# LOGIC_CONNECTOR.net
KiCad netlist of a schematic drawn in Altium Designer
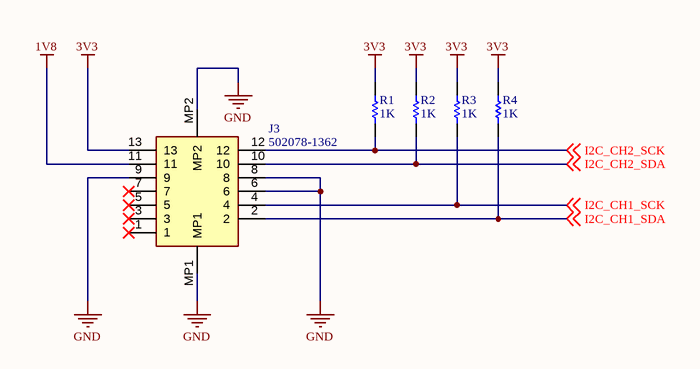
[diagram p0: LOGIC_CONNECTOR.SchDoc]

(export (version "E")
  (design (tool "Eeschema 10.0.6"))
  (components
    (comp (ref "J3")
      (value "502078-1362")
      (footprint "SamacSys:5020781362")
      (description "Connector")
      (fields (field (name "MOUSER PART NUMBER") "538-502078-1362"))
      (libsource (lib "*") (part "502078-1362"))
    )
    (comp (ref "R1")
      (value "1K")
      (footprint "RESC1005X40X25LL05T10")
      (fields (field (name "PART NUMBER") "RC0402JR-071KL") (field (name "MANUFACTURER") "Yageo / Phycomp"))
      (libsource (lib "Altium Content Vault") (part "RES"))
    )
    (comp (ref "R2")
      (value "1K")
      (footprint "RESC1005X40X25LL05T10")
      (fields (field (name "PART NUMBER") "RC0402JR-071KL") (field (name "MANUFACTURER") "Yageo / Phycomp"))
      (libsource (lib "Altium Content Vault") (part "RES"))
    )
    (comp (ref "R3")
      (value "1K")
      (footprint "RESC1005X40X25LL05T10")
      (fields (field (name "PART NUMBER") "RC0402JR-071KL") (field (name "MANUFACTURER") "Yageo / Phycomp"))
      (libsource (lib "Altium Content Vault") (part "RES"))
    )
    (comp (ref "R4")
      (value "1K")
      (footprint "RESC1005X40X25LL05T10")
      (fields (field (name "PART NUMBER") "RC0402JR-071KL") (field (name "MANUFACTURER") "Yageo / Phycomp"))
      (libsource (lib "Altium Content Vault") (part "RES"))
    )
  )
  (nets
    (net (code "1") (name "1V8") (class "Default")
      (node (ref "J3") (pin "11") (pinfunction "11_11") (pintype "passive"))
    )
    (net (code "2") (name "3V3") (class "Default")
      (node (ref "J3") (pin "13") (pinfunction "13_13") (pintype "passive"))
      (node (ref "R1") (pin "2") (pinfunction "2_2") (pintype "passive"))
      (node (ref "R2") (pin "2") (pinfunction "2_2") (pintype "passive"))
      (node (ref "R3") (pin "2") (pinfunction "2_2") (pintype "passive"))
      (node (ref "R4") (pin "2") (pinfunction "2_2") (pintype "passive"))
    )
    (net (code "3") (name "GND") (class "Default")
      (node (ref "J3") (pin "6") (pinfunction "6_6") (pintype "passive"))
      (node (ref "J3") (pin "8") (pinfunction "8_8") (pintype "passive"))
      (node (ref "J3") (pin "9") (pinfunction "9_9") (pintype "passive"))
      (node (ref "J3") (pin "MP1") (pinfunction "MP1_MP1") (pintype "passive"))
      (node (ref "J3") (pin "MP2") (pinfunction "MP2_MP2") (pintype "passive"))
    )
    (net (code "4") (name "I2C_CH1_SCK") (class "Default")
      (node (ref "J3") (pin "4") (pinfunction "4_4") (pintype "passive"))
      (node (ref "R3") (pin "1") (pinfunction "1_1") (pintype "passive"))
    )
    (net (code "5") (name "I2C_CH1_SDA") (class "Default")
      (node (ref "J3") (pin "2") (pinfunction "2_2") (pintype "passive"))
      (node (ref "R4") (pin "1") (pinfunction "1_1") (pintype "passive"))
    )
    (net (code "6") (name "I2C_CH2_SCK") (class "Default")
      (node (ref "J3") (pin "12") (pinfunction "12_12") (pintype "passive"))
      (node (ref "R1") (pin "1") (pinfunction "1_1") (pintype "passive"))
    )
    (net (code "7") (name "I2C_CH2_SDA") (class "Default")
      (node (ref "J3") (pin "10") (pinfunction "10_10") (pintype "passive"))
      (node (ref "R2") (pin "1") (pinfunction "1_1") (pintype "passive"))
    )
    (net (code "8") (name "unconnected-(J3-Pad1)") (class "Default")
      (node (ref "J3") (pin "1") (pinfunction "1_1") (pintype "passive+no_connect"))
    )
    (net (code "9") (name "unconnected-(J3-Pad3)") (class "Default")
      (node (ref "J3") (pin "3") (pinfunction "3_3") (pintype "passive+no_connect"))
    )
    (net (code "10") (name "unconnected-(J3-Pad5)") (class "Default")
      (node (ref "J3") (pin "5") (pinfunction "5_5") (pintype "passive+no_connect"))
    )
    (net (code "11") (name "unconnected-(J3-Pad7)") (class "Default")
      (node (ref "J3") (pin "7") (pinfunction "7_7") (pintype "passive+no_connect"))
    )
  )
)
